# Power.net
KiCad netlist of a schematic drawn in Altium Designer
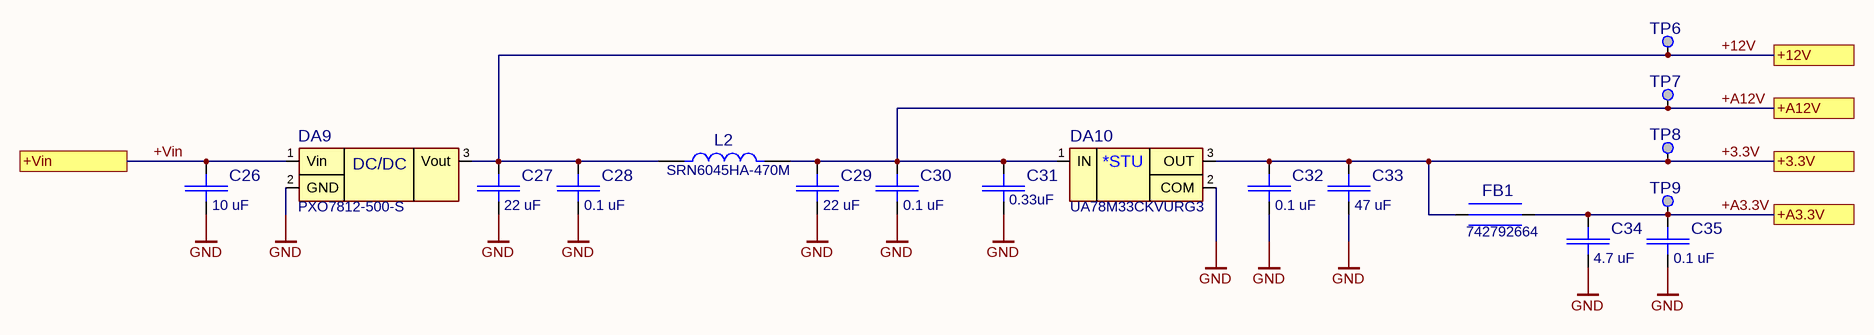
[diagram p0: Power.SchDoc]

(export (version "E")
  (design (tool "Eeschema 10.0.6"))
  (components
    (comp (ref "C26")
      (value "10 uF")
      (footprint "Capacitor0805_THICKNESS1.45")
      (description "Multilayer Ceramic Capacitors MLCC - SMD/SMT 10 uF 35 VDC 10% 0805 X5R")
      (fields (field (name "TOLERANCE") "10%") (field (name "MANUFACTURERPARTNUMBER") "GRM21BR6YA106KE43K"))
      (libsource (lib "NGI_Search") (part "GRM21BR6YA106KE43K"))
    )
    (comp (ref "C27")
      (value "22 uF")
      (footprint "Capacitor1206_THICKNESS1.6")
      (description "Multilayer Ceramic Capacitors MLCC - SMD/SMT 1206 35V 22uF X5R 20% T: 1.6mm")
      (fields
        (field (name "MANUFACTURER") "TDK")
        (field (name "MANUFACTURERPARTNUMBER") "C3216X5R1V226M160AC")
      )
      (libsource (lib "NGI_Search") (part "C3216X5R1V226M160AC"))
    )
    (comp (ref "C28")
      (value "0.1 uF")
      (footprint "Capacitor0805_THICKNESS0.8")
      (description "Multilayer Ceramic Capacitors MLCC - SMD/SMT 100nF+/-10% 50V X7R 0805")
      (fields (field (name "TOLERANCE") "10%") (field (name "MANUFACTURERPARTNUMBER") "CL21B104KBCNNWC"))
      (libsource (lib "NGI_Search") (part "CL21B104KBCNNWC"))
    )
    (comp (ref "C29")
      (value "22 uF")
      (footprint "Capacitor1206_THICKNESS1.6")
      (description "Multilayer Ceramic Capacitors MLCC - SMD/SMT 1206 35V 22uF X5R 20% T: 1.6mm")
      (fields
        (field (name "MANUFACTURER") "TDK")
        (field (name "MANUFACTURERPARTNUMBER") "C3216X5R1V226M160AC")
      )
      (libsource (lib "NGI_Search") (part "C3216X5R1V226M160AC"))
    )
    (comp (ref "C30")
      (value "0.1 uF")
      (footprint "Capacitor0805_THICKNESS0.8")
      (description "Multilayer Ceramic Capacitors MLCC - SMD/SMT 100nF+/-10% 50V X7R 0805")
      (fields (field (name "TOLERANCE") "10%") (field (name "MANUFACTURERPARTNUMBER") "CL21B104KBCNNWC"))
      (libsource (lib "NGI_Search") (part "CL21B104KBCNNWC"))
    )
    (comp (ref "C31")
      (value "0.33uF")
      (footprint "Capacitor0805_THICKNESS1.25")
      (description "Multilayer Ceramic Capacitors MLCC - SMD/SMT 25V 0.33uF X7R 0805 10%")
      (fields
        (field (name "MANUFACTURER") "YAGEO")
        (field (name "MANUFACTURERPARTNUMBER") "CC0805KKX7R8BB334")
      )
      (libsource (lib "NGI_Search") (part "CC0805KKX7R8BB334"))
    )
    (comp (ref "C32")
      (value "0.1 uF")
      (footprint "Capacitor0805_THICKNESS0.8")
      (description "Multilayer Ceramic Capacitors MLCC - SMD/SMT 100nF+/-10% 50V X7R 0805")
      (fields (field (name "TOLERANCE") "10%") (field (name "MANUFACTURERPARTNUMBER") "CL21B104KBCNNWC"))
      (libsource (lib "NGI_Search") (part "CL21B104KBCNNWC"))
    )
    (comp (ref "C33")
      (value "47 uF")
      (footprint "Capacitor0805_THICKNESS1.25")
      (description "Multilayer Ceramic Capacitors MLCC - SMD/SMT 47 uF 10 VDC 20% 0805 X5R")
      (fields
        (field (name "MANUFACTURER") "Murata")
        (field (name "MANUFACTURERPARTNUMBER") "GRM21BR61A476ME15K")
      )
      (libsource (lib "NGI_Search") (part "GRM21BR61A476ME15K"))
    )
    (comp (ref "C34")
      (value "4.7 uF")
      (footprint "Capacitor0805_THICKNESS1.25")
      (description "Multilayer Ceramic Capacitors MLCC - SMD/SMT 4.7uF+/-10% 25V X5R 0805")
      (fields
        (field (name "MANUFACTURER") "Samsung Electro-Mechanics")
        (field (name "MANUFACTURERPARTNUMBER") "CL21A475KAQNNNF")
      )
      (libsource (lib "NGI_Search") (part "CL21A475KAQNNNF"))
    )
    (comp (ref "C35")
      (value "0.1 uF")
      (footprint "Capacitor0805_THICKNESS0.8")
      (description "Multilayer Ceramic Capacitors MLCC - SMD/SMT 100nF+/-10% 50V X7R 0805")
      (fields (field (name "TOLERANCE") "10%") (field (name "MANUFACTURERPARTNUMBER") "CL21B104KBCNNWC"))
      (libsource (lib "NGI_Search") (part "CL21B104KBCNNWC"))
    )
    (comp (ref "DA9")
      (value "PXO7812-500-S")
      (footprint "PXO7812-500-S_POSITIVEOUTPUT")
      (description "Non-Isolated DC/DC Converters dc-dc non-isolated, 0.5 A, 15-36 Vdc input, 12 Vdc output, SIP")
      (fields
        (field (name "MANUFACTURER") "CUI Inc.")
        (field (name "MOUSER PART NUMBER") "490-PXO7812-500-S")
      )
      (libsource (lib "NGI_Search") (part "PXO7812-500-S"))
    )
    (comp (ref "DA10")
      (value "UA78M33CKVURG3")
      (footprint "TO-252 3pin THICKNESS2.52")
      (description "Linear Voltage Regulators 3.3 V 500mA Fix Pos Voltage Regulator")
      (fields
        (field (name "MANUFACTURER") "Texas Instruments")
        (field (name "MOUSER PART NUMBER") "595-UA78M33CKVURG3")
      )
      (libsource (lib "NGI_Search") (part "UA78M33CKVURG3"))
    )
    (comp (ref "FB1")
      (value "742792664")
      (footprint "742792664_Ferrite Beads_0603")
      (description "Ferrite Beads WE-CBF 0603 100MHz 1000Ohm 300mA AEC-Q200")
      (fields
        (field (name "MANUFACTURER") "Wurth Elektronik")
        (field (name "MOUSER PART NUMBER") "710-742792664")
      )
      (libsource (lib "NGI_Search") (part "742792664"))
    )
    (comp (ref "L2")
      (value "SRN6045HA-470M")
      (footprint "SRN6045HA-470M")
      (description "Power Inductors - SMD Ind,6x6x4.7mm,47uH+/-20%,1A,semi-shd")
      (fields (field (name "MANUFACTURER") "Bourns") (field (name "MOUSER PART NUMBER") "652-SRN6045HA-470M"))
      (libsource (lib "NGI_Search") (part "SRN6045HA-470M"))
    )
    (comp (ref "TP6")
      (value "test point")
      (footprint "test point")
      (libsource (lib "NGI_Search") (part "test point"))
    )
    (comp (ref "TP7")
      (value "test point")
      (footprint "test point")
      (libsource (lib "NGI_Search") (part "test point"))
    )
    (comp (ref "TP8")
      (value "test point")
      (footprint "test point")
      (libsource (lib "NGI_Search") (part "test point"))
    )
    (comp (ref "TP9")
      (value "test point")
      (footprint "test point")
      (libsource (lib "NGI_Search") (part "test point"))
    )
  )
  (nets
    (net (code "1") (name "/+3.3V") (class "Default")
      (node (ref "C32") (pin "2") (pinfunction "2_2") (pintype "passive"))
      (node (ref "C33") (pin "2") (pinfunction "2_2") (pintype "passive"))
      (node (ref "DA10") (pin "3") (pinfunction "OUT_3") (pintype "passive"))
      (node (ref "FB1") (pin "1") (pinfunction "1_1") (pintype "passive"))
      (node (ref "TP8") (pin "1") (pinfunction "1_1") (pintype "passive"))
    )
    (net (code "2") (name "/+12V") (class "Default")
      (node (ref "C27") (pin "2") (pinfunction "2_2") (pintype "passive"))
      (node (ref "C28") (pin "2") (pinfunction "2_2") (pintype "passive"))
      (node (ref "DA9") (pin "3") (pinfunction "Vout_3") (pintype "passive"))
      (node (ref "L2") (pin "1") (pinfunction "1_1") (pintype "passive"))
      (node (ref "TP6") (pin "1") (pinfunction "1_1") (pintype "passive"))
    )
    (net (code "3") (name "/+A3.3V") (class "Default")
      (node (ref "C34") (pin "2") (pinfunction "2_2") (pintype "passive"))
      (node (ref "C35") (pin "2") (pinfunction "2_2") (pintype "passive"))
      (node (ref "FB1") (pin "2") (pinfunction "2_2") (pintype "passive"))
      (node (ref "TP9") (pin "1") (pinfunction "1_1") (pintype "passive"))
    )
    (net (code "4") (name "/+A12V") (class "Default")
      (node (ref "C29") (pin "2") (pinfunction "2_2") (pintype "passive"))
      (node (ref "C30") (pin "2") (pinfunction "2_2") (pintype "passive"))
      (node (ref "C31") (pin "2") (pinfunction "2_2") (pintype "passive"))
      (node (ref "DA10") (pin "1") (pinfunction "IN_1") (pintype "passive"))
      (node (ref "L2") (pin "2") (pinfunction "2_2") (pintype "passive"))
      (node (ref "TP7") (pin "1") (pinfunction "1_1") (pintype "passive"))
    )
    (net (code "5") (name "/+Vin") (class "Default")
      (node (ref "C26") (pin "2") (pinfunction "2_2") (pintype "passive"))
      (node (ref "DA9") (pin "1") (pinfunction "Vin_1") (pintype "passive"))
    )
    (net (code "6") (name "GND") (class "Default")
      (node (ref "C26") (pin "1") (pinfunction "1_1") (pintype "passive"))
      (node (ref "C27") (pin "1") (pinfunction "1_1") (pintype "passive"))
      (node (ref "C28") (pin "1") (pinfunction "1_1") (pintype "passive"))
      (node (ref "C29") (pin "1") (pinfunction "1_1") (pintype "passive"))
      (node (ref "C30") (pin "1") (pinfunction "1_1") (pintype "passive"))
      (node (ref "C31") (pin "1") (pinfunction "1_1") (pintype "passive"))
      (node (ref "C32") (pin "1") (pinfunction "1_1") (pintype "passive"))
      (node (ref "C33") (pin "1") (pinfunction "1_1") (pintype "passive"))
      (node (ref "C34") (pin "1") (pinfunction "1_1") (pintype "passive"))
      (node (ref "C35") (pin "1") (pinfunction "1_1") (pintype "passive"))
      (node (ref "DA10") (pin "2") (pinfunction "COM_2") (pintype "power_in"))
      (node (ref "DA9") (pin "2") (pinfunction "GND_2") (pintype "power_in"))
    )
  )
)
